# design.net
KiCad netlist of a schematic drawn in EasyEDA Pro
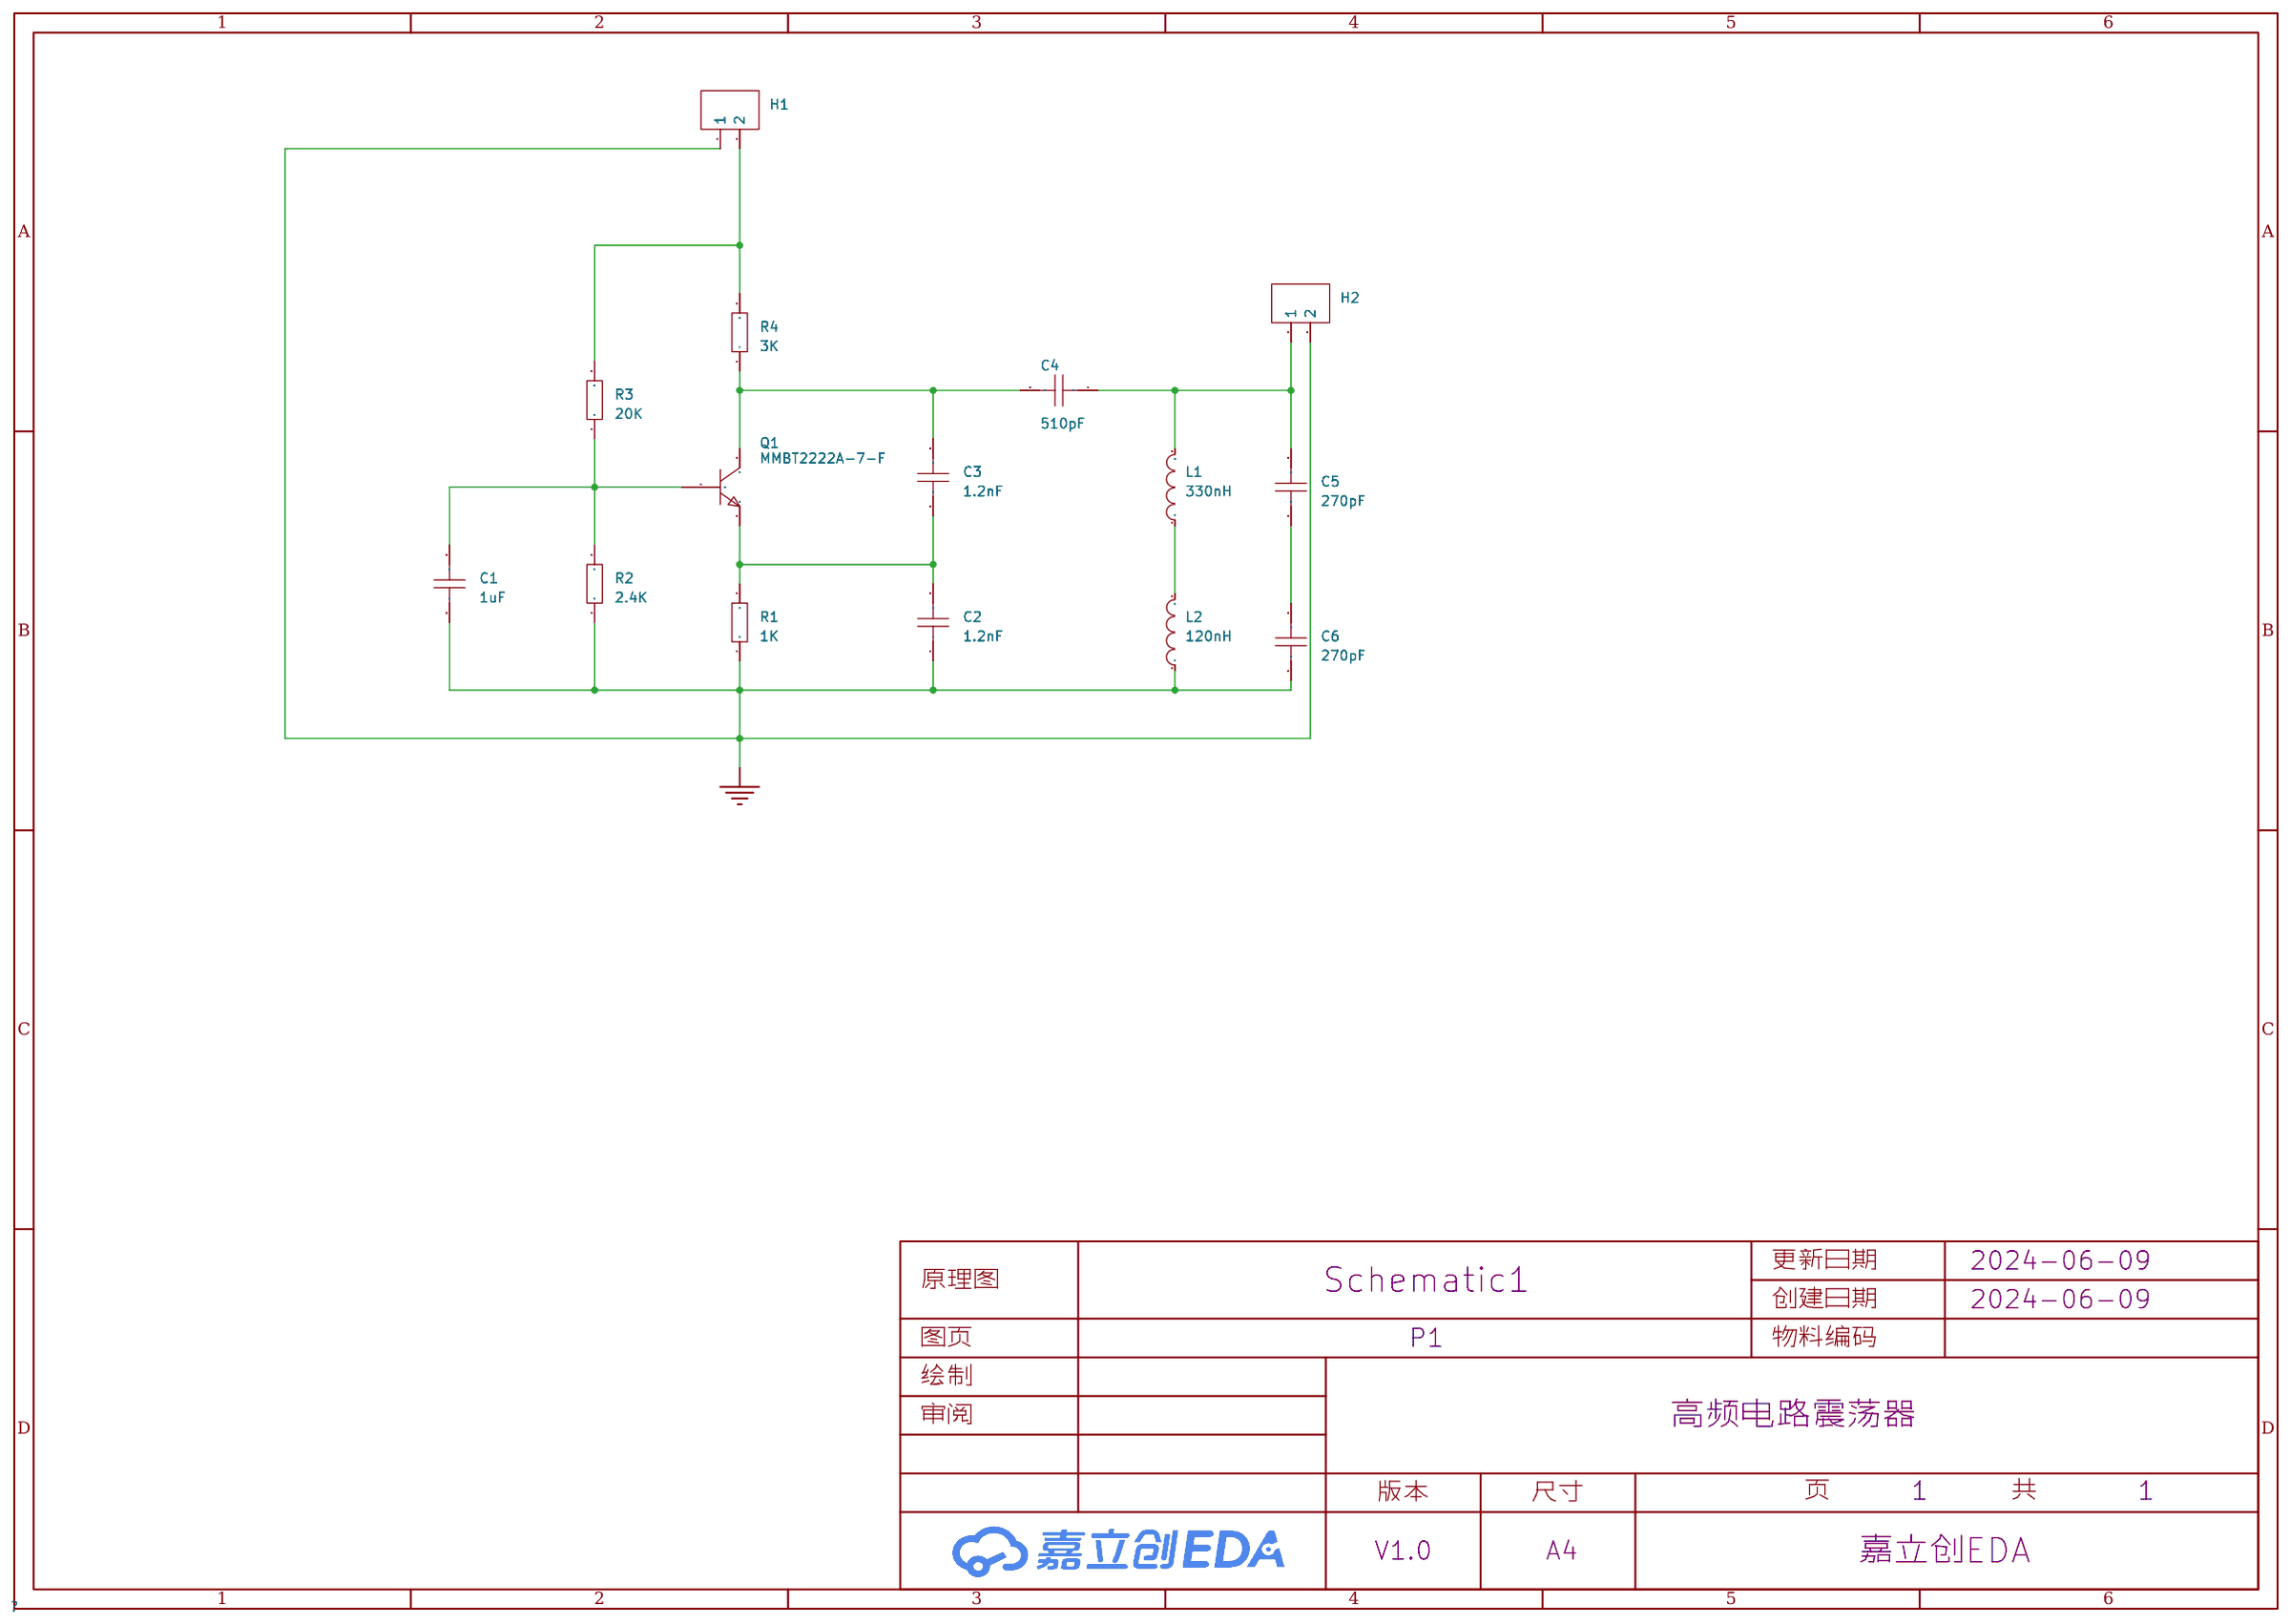
[diagram p0: schematic sheet]

(export (version "E")
  (design (tool "Eeschema 10.0.6"))
  (components
    (comp (ref "C1")
      (value "1uF")
      (footprint "easyedapro:C0805")
      (libsource (lib "easyedapro") (part "CapAcitance"))
    )
    (comp (ref "C2")
      (value "1.2nF")
      (footprint "easyedapro:C0805")
      (libsource (lib "easyedapro") (part "CapAcitance"))
    )
    (comp (ref "C3")
      (value "1.2nF")
      (footprint "easyedapro:C0805")
      (libsource (lib "easyedapro") (part "CapAcitance"))
    )
    (comp (ref "C4")
      (value "510pF")
      (footprint "easyedapro:C0805")
      (libsource (lib "easyedapro") (part "CapAcitance"))
    )
    (comp (ref "C5")
      (value "270pF")
      (footprint "easyedapro:C0805")
      (libsource (lib "easyedapro") (part "CapAcitance"))
    )
    (comp (ref "C6")
      (value "270pF")
      (footprint "easyedapro:C0805")
      (libsource (lib "easyedapro") (part "CapAcitance"))
    )
    (comp (ref "H1")
      (value "~")
      (footprint "easyedapro:HDR-TH_2P-P2.54-V-F")
      (libsource (lib "easyedapro") (part "Header-Female-2.54_1x2"))
    )
    (comp (ref "H2")
      (value "~")
      (footprint "easyedapro:HDR-TH_2P-P2.54-V-F")
      (libsource (lib "easyedapro") (part "Header-Female-2.54_1x2"))
    )
    (comp (ref "L1")
      (value "330nH")
      (footprint "easyedapro:L0805")
      (libsource (lib "easyedapro") (part "SDFL2012S100KTF"))
    )
    (comp (ref "L2")
      (value "120nH")
      (footprint "easyedapro:L0805")
      (libsource (lib "easyedapro") (part "SDFL2012S100KTF"))
    )
    (comp (ref "Q1")
      (value "MMBT2222A-7-F")
      (footprint "easyedapro:SOT-23-3_L2.9-W1.6-P1.90-LS2.8-BR")
      (description "晶体管类型:NPN;集电极电流(Ic):600mA;集射极击穿电压(Vceo):40V;功率(Pd):310mW;直流电流增益(hFE@Ic,Vce):100@150mA,10V;")
      (fields (field (name "Manufacturer") "DIODES(美台)"))
      (libsource (lib "easyedapro") (part "MMBT2222A-7-F"))
    )
    (comp (ref "R1") (value "1K") (footprint "easyedapro:R0805") (libsource (lib "easyedapro") (part "电阻")))
    (comp (ref "R2") (value "2.4K") (footprint "easyedapro:R0805") (libsource (lib "easyedapro") (part "电阻")))
    (comp (ref "R3") (value "20K") (footprint "easyedapro:R0805") (libsource (lib "easyedapro") (part "电阻")))
    (comp (ref "R4") (value "3K") (footprint "easyedapro:R0805") (libsource (lib "easyedapro") (part "电阻")))
  )
  (nets
    (net (code "1") (name "GND") (class "Default")
      (node (ref "C1") (pin "2") (pinfunction "2_2") (pintype "input"))
      (node (ref "C2") (pin "1") (pinfunction "1_1") (pintype "input"))
      (node (ref "C6") (pin "1") (pinfunction "1_1") (pintype "input"))
      (node (ref "H1") (pin "1") (pinfunction "1_1") (pintype "input"))
      (node (ref "H2") (pin "2") (pinfunction "2_2") (pintype "input"))
      (node (ref "L2") (pin "1") (pinfunction "1_1") (pintype "input"))
      (node (ref "R1") (pin "1") (pinfunction "1_1") (pintype "input"))
      (node (ref "R2") (pin "1") (pinfunction "1_1") (pintype "input"))
    )
    (net (code "2") (name "Net-(C4-Pad1)") (class "Default")
      (node (ref "C4") (pin "1") (pinfunction "1_1") (pintype "input"))
      (node (ref "C5") (pin "2") (pinfunction "2_2") (pintype "input"))
      (node (ref "H2") (pin "1") (pinfunction "1_1") (pintype "input"))
      (node (ref "L1") (pin "2") (pinfunction "2_2") (pintype "input"))
    )
    (net (code "3") (name "Net-(C5-Pad1)") (class "Default")
      (node (ref "C5") (pin "1") (pinfunction "1_1") (pintype "input"))
      (node (ref "C6") (pin "2") (pinfunction "2_2") (pintype "input"))
    )
    (net (code "4") (name "Net-(H1-Pad2)") (class "Default")
      (node (ref "H1") (pin "2") (pinfunction "2_2") (pintype "input"))
      (node (ref "R3") (pin "2") (pinfunction "2_2") (pintype "input"))
      (node (ref "R4") (pin "2") (pinfunction "2_2") (pintype "input"))
    )
    (net (code "5") (name "Net-(L1-Pad1)") (class "Default")
      (node (ref "L1") (pin "1") (pinfunction "1_1") (pintype "input"))
      (node (ref "L2") (pin "2") (pinfunction "2_2") (pintype "input"))
    )
    (net (code "6") (name "Net-(Q1-B)") (class "Default")
      (node (ref "C1") (pin "1") (pinfunction "1_1") (pintype "input"))
      (node (ref "Q1") (pin "1") (pinfunction "B_1") (pintype "unspecified"))
      (node (ref "R2") (pin "2") (pinfunction "2_2") (pintype "input"))
      (node (ref "R3") (pin "1") (pinfunction "1_1") (pintype "input"))
    )
    (net (code "7") (name "Net-(Q1-C)") (class "Default")
      (node (ref "C3") (pin "2") (pinfunction "2_2") (pintype "input"))
      (node (ref "C4") (pin "2") (pinfunction "2_2") (pintype "input"))
      (node (ref "Q1") (pin "3") (pinfunction "C_3") (pintype "unspecified"))
      (node (ref "R4") (pin "1") (pinfunction "1_1") (pintype "input"))
    )
    (net (code "8") (name "Net-(Q1-E)") (class "Default")
      (node (ref "C2") (pin "2") (pinfunction "2_2") (pintype "input"))
      (node (ref "C3") (pin "1") (pinfunction "1_1") (pintype "input"))
      (node (ref "Q1") (pin "2") (pinfunction "E_2") (pintype "unspecified"))
      (node (ref "R1") (pin "2") (pinfunction "2_2") (pintype "input"))
    )
  )
)
